# POVRotor.net
KiCad netlist of a schematic drawn in EAGLE
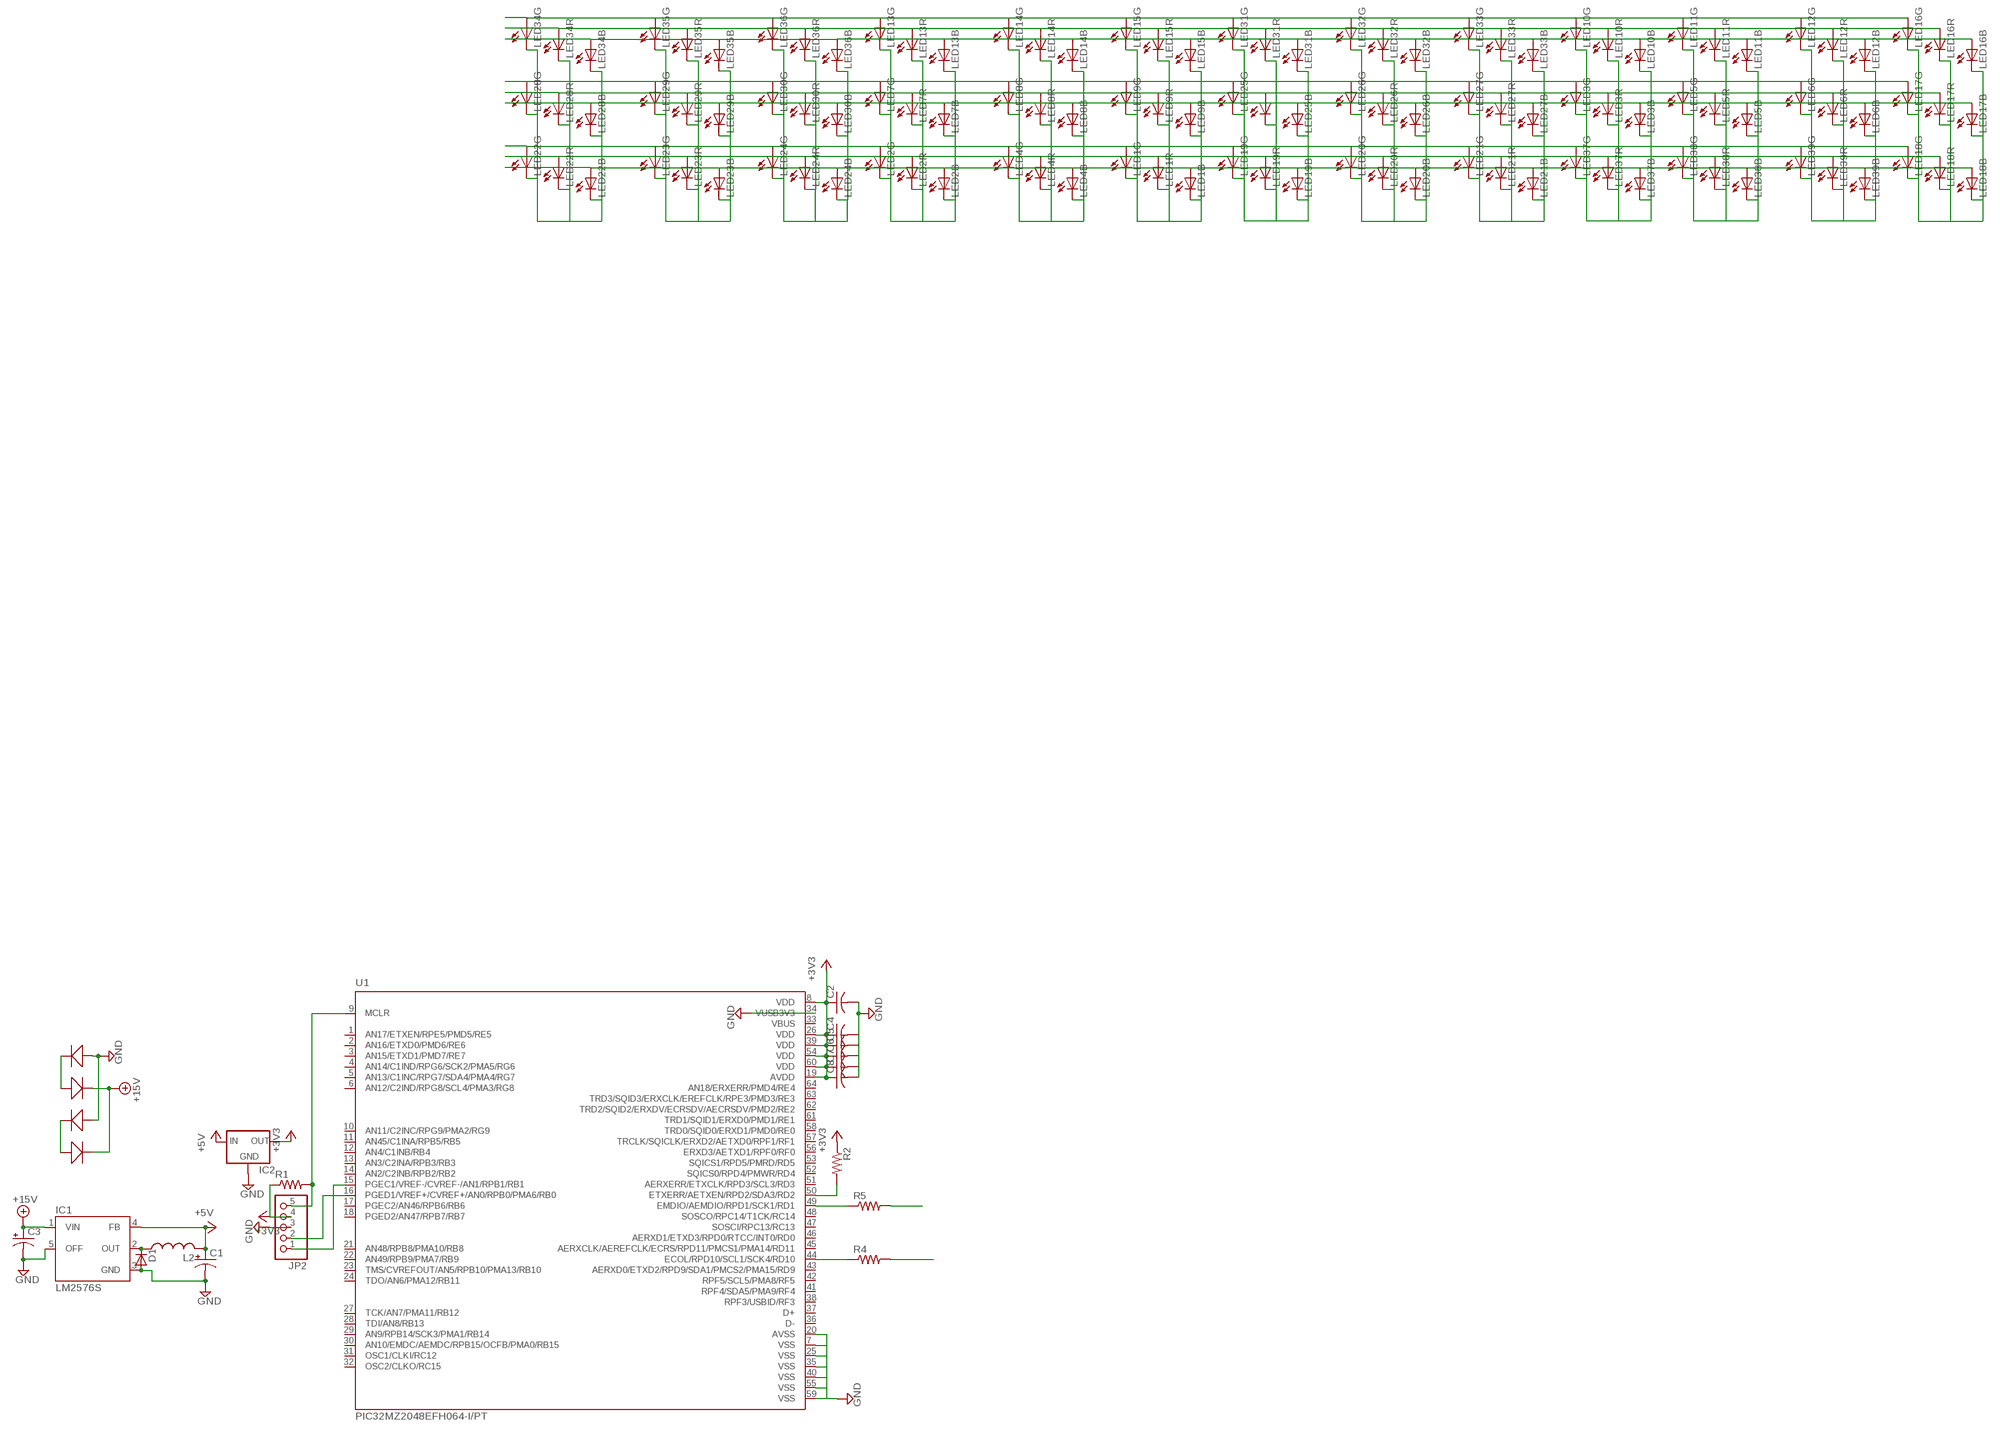
[diagram p0: schematic, sheet 1]

(export (version "E")
  (design (tool "Eeschema 10.0.6"))
  (components
    (comp (ref "C1")
      (value "CPOL-USE2,5-6E")
      (footprint "eagle-import:E2,5-6E")
      (libsource (lib "eagle-import") (part "CPOL-USE2,5-6E"))
    )
    (comp (ref "C2")
      (value "C-USC0805")
      (footprint "eagle-import:C0805")
      (libsource (lib "eagle-import") (part "C-USC0805"))
    )
    (comp (ref "C3")
      (value "CPOL-USE2,5-6E")
      (footprint "eagle-import:E2,5-6E")
      (libsource (lib "eagle-import") (part "CPOL-USE2,5-6E"))
    )
    (comp (ref "C4")
      (value "C-USC0805")
      (footprint "eagle-import:C0805")
      (libsource (lib "eagle-import") (part "C-USC0805"))
    )
    (comp (ref "C5")
      (value "C-USC0805")
      (footprint "eagle-import:C0805")
      (libsource (lib "eagle-import") (part "C-USC0805"))
    )
    (comp (ref "C6")
      (value "C-USC0805")
      (footprint "eagle-import:C0805")
      (libsource (lib "eagle-import") (part "C-USC0805"))
    )
    (comp (ref "C7")
      (value "C-USC0805")
      (footprint "eagle-import:C0805")
      (libsource (lib "eagle-import") (part "C-USC0805"))
    )
    (comp (ref "C8")
      (value "C-USC0805")
      (footprint "eagle-import:C0805")
      (libsource (lib "eagle-import") (part "C-USC0805"))
    )
    (comp (ref "D1")
      (value "BYS10")
      (footprint "eagle-import:SOD106A")
      (fields (field (name "MPN") "BYS10/45"))
      (libsource (lib "eagle-import") (part "BYS10"))
    )
    (comp (ref "D2")
      (value "SMD-DIODE-SCHOTTKY-40V-3A(DO-214AB)")
      (footprint "eagle-import:DO-214AB")
      (fields (field (name "MF") "Vishay") (field (name "MP") "SS34-E3/57T"))
      (libsource (lib "eagle-import") (part "SMD-DIODE-SCHOTTKY-40V-3A(DO-214AB)"))
    )
    (comp (ref "D3")
      (value "SMD-DIODE-SCHOTTKY-40V-3A(DO-214AB)")
      (footprint "eagle-import:DO-214AB")
      (fields (field (name "MF") "Vishay") (field (name "MP") "SS34-E3/57T"))
      (libsource (lib "eagle-import") (part "SMD-DIODE-SCHOTTKY-40V-3A(DO-214AB)"))
    )
    (comp (ref "D4")
      (value "SMD-DIODE-SCHOTTKY-40V-3A(DO-214AB)")
      (footprint "eagle-import:DO-214AB")
      (fields (field (name "MF") "Vishay") (field (name "MP") "SS34-E3/57T"))
      (libsource (lib "eagle-import") (part "SMD-DIODE-SCHOTTKY-40V-3A(DO-214AB)"))
    )
    (comp (ref "D5")
      (value "SMD-DIODE-SCHOTTKY-40V-3A(DO-214AB)")
      (footprint "eagle-import:DO-214AB")
      (fields (field (name "MF") "Vishay") (field (name "MP") "SS34-E3/57T"))
      (libsource (lib "eagle-import") (part "SMD-DIODE-SCHOTTKY-40V-3A(DO-214AB)"))
    )
    (comp (ref "IC1")
      (value "LM2576S")
      (footprint "eagle-import:TO263-5")
      (libsource (lib "eagle-import") (part "LM2576S"))
    )
    (comp (ref "IC2")
      (value "LM1117")
      (footprint "eagle-import:SOT223")
      (libsource (lib "eagle-import") (part "LM1117"))
    )
    (comp (ref "JP2")
      (value "PINHD-1X5")
      (footprint "eagle-import:1X05")
      (libsource (lib "eagle-import") (part "PINHD-1X5"))
    )
    (comp (ref "L2")
      (value "L-USL4532P")
      (footprint "eagle-import:L4532P")
      (libsource (lib "eagle-import") (part "L-USL4532P"))
    )
    (comp (ref "LED1")
      (value "LP2C63-ST-RGB-SR0")
      (footprint "eagle-import:LP2C63-ST-RGB-SR0")
      (libsource (lib "eagle-import") (part "LP2C63-ST-RGB-SR0"))
    )
    (comp (ref "LED2")
      (value "LP2C63-ST-RGB-SR0")
      (footprint "eagle-import:LP2C63-ST-RGB-SR0")
      (libsource (lib "eagle-import") (part "LP2C63-ST-RGB-SR0"))
    )
    (comp (ref "LED3")
      (value "LP2C63-ST-RGB-SR0")
      (footprint "eagle-import:LP2C63-ST-RGB-SR0")
      (libsource (lib "eagle-import") (part "LP2C63-ST-RGB-SR0"))
    )
    (comp (ref "LED4")
      (value "LP2C63-ST-RGB-SR0")
      (footprint "eagle-import:LP2C63-ST-RGB-SR0")
      (libsource (lib "eagle-import") (part "LP2C63-ST-RGB-SR0"))
    )
    (comp (ref "LED5")
      (value "LP2C63-ST-RGB-SR0")
      (footprint "eagle-import:LP2C63-ST-RGB-SR0")
      (libsource (lib "eagle-import") (part "LP2C63-ST-RGB-SR0"))
    )
    (comp (ref "LED6")
      (value "LP2C63-ST-RGB-SR0")
      (footprint "eagle-import:LP2C63-ST-RGB-SR0")
      (libsource (lib "eagle-import") (part "LP2C63-ST-RGB-SR0"))
    )
    (comp (ref "LED7")
      (value "LP2C63-ST-RGB-SR0")
      (footprint "eagle-import:LP2C63-ST-RGB-SR0")
      (libsource (lib "eagle-import") (part "LP2C63-ST-RGB-SR0"))
    )
    (comp (ref "LED8")
      (value "LP2C63-ST-RGB-SR0")
      (footprint "eagle-import:LP2C63-ST-RGB-SR0")
      (libsource (lib "eagle-import") (part "LP2C63-ST-RGB-SR0"))
    )
    (comp (ref "LED9")
      (value "LP2C63-ST-RGB-SR0")
      (footprint "eagle-import:LP2C63-ST-RGB-SR0")
      (libsource (lib "eagle-import") (part "LP2C63-ST-RGB-SR0"))
    )
    (comp (ref "LED10")
      (value "LP2C63-ST-RGB-SR0")
      (footprint "eagle-import:LP2C63-ST-RGB-SR0")
      (libsource (lib "eagle-import") (part "LP2C63-ST-RGB-SR0"))
    )
    (comp (ref "LED11")
      (value "LP2C63-ST-RGB-SR0")
      (footprint "eagle-import:LP2C63-ST-RGB-SR0")
      (libsource (lib "eagle-import") (part "LP2C63-ST-RGB-SR0"))
    )
    (comp (ref "LED12")
      (value "LP2C63-ST-RGB-SR0")
      (footprint "eagle-import:LP2C63-ST-RGB-SR0")
      (libsource (lib "eagle-import") (part "LP2C63-ST-RGB-SR0"))
    )
    (comp (ref "LED13")
      (value "LP2C63-ST-RGB-SR0")
      (footprint "eagle-import:LP2C63-ST-RGB-SR0")
      (libsource (lib "eagle-import") (part "LP2C63-ST-RGB-SR0"))
    )
    (comp (ref "LED14")
      (value "LP2C63-ST-RGB-SR0")
      (footprint "eagle-import:LP2C63-ST-RGB-SR0")
      (libsource (lib "eagle-import") (part "LP2C63-ST-RGB-SR0"))
    )
    (comp (ref "LED15")
      (value "LP2C63-ST-RGB-SR0")
      (footprint "eagle-import:LP2C63-ST-RGB-SR0")
      (libsource (lib "eagle-import") (part "LP2C63-ST-RGB-SR0"))
    )
    (comp (ref "LED16")
      (value "LP2C63-ST-RGB-SR0")
      (footprint "eagle-import:LP2C63-ST-RGB-SR0")
      (libsource (lib "eagle-import") (part "LP2C63-ST-RGB-SR0"))
    )
    (comp (ref "LED17")
      (value "LP2C63-ST-RGB-SR0")
      (footprint "eagle-import:LP2C63-ST-RGB-SR0")
      (libsource (lib "eagle-import") (part "LP2C63-ST-RGB-SR0"))
    )
    (comp (ref "LED18")
      (value "LP2C63-ST-RGB-SR0")
      (footprint "eagle-import:LP2C63-ST-RGB-SR0")
      (libsource (lib "eagle-import") (part "LP2C63-ST-RGB-SR0"))
    )
    (comp (ref "LED19")
      (value "LP2C63-ST-RGB-SR0")
      (footprint "eagle-import:LP2C63-ST-RGB-SR0")
      (libsource (lib "eagle-import") (part "LP2C63-ST-RGB-SR0"))
    )
    (comp (ref "LED20")
      (value "LP2C63-ST-RGB-SR0")
      (footprint "eagle-import:LP2C63-ST-RGB-SR0")
      (libsource (lib "eagle-import") (part "LP2C63-ST-RGB-SR0"))
    )
    (comp (ref "LED21")
      (value "LP2C63-ST-RGB-SR0")
      (footprint "eagle-import:LP2C63-ST-RGB-SR0")
      (libsource (lib "eagle-import") (part "LP2C63-ST-RGB-SR0"))
    )
    (comp (ref "LED22")
      (value "LP2C63-ST-RGB-SR0")
      (footprint "eagle-import:LP2C63-ST-RGB-SR0")
      (libsource (lib "eagle-import") (part "LP2C63-ST-RGB-SR0"))
    )
    (comp (ref "LED23")
      (value "LP2C63-ST-RGB-SR0")
      (footprint "eagle-import:LP2C63-ST-RGB-SR0")
      (libsource (lib "eagle-import") (part "LP2C63-ST-RGB-SR0"))
    )
    (comp (ref "LED24")
      (value "LP2C63-ST-RGB-SR0")
      (footprint "eagle-import:LP2C63-ST-RGB-SR0")
      (libsource (lib "eagle-import") (part "LP2C63-ST-RGB-SR0"))
    )
    (comp (ref "LED25")
      (value "LP2C63-ST-RGB-SR0")
      (footprint "eagle-import:LP2C63-ST-RGB-SR0")
      (libsource (lib "eagle-import") (part "LP2C63-ST-RGB-SR0"))
    )
    (comp (ref "LED26")
      (value "LP2C63-ST-RGB-SR0")
      (footprint "eagle-import:LP2C63-ST-RGB-SR0")
      (libsource (lib "eagle-import") (part "LP2C63-ST-RGB-SR0"))
    )
    (comp (ref "LED27")
      (value "LP2C63-ST-RGB-SR0")
      (footprint "eagle-import:LP2C63-ST-RGB-SR0")
      (libsource (lib "eagle-import") (part "LP2C63-ST-RGB-SR0"))
    )
    (comp (ref "LED28")
      (value "LP2C63-ST-RGB-SR0")
      (footprint "eagle-import:LP2C63-ST-RGB-SR0")
      (libsource (lib "eagle-import") (part "LP2C63-ST-RGB-SR0"))
    )
    (comp (ref "LED29")
      (value "LP2C63-ST-RGB-SR0")
      (footprint "eagle-import:LP2C63-ST-RGB-SR0")
      (libsource (lib "eagle-import") (part "LP2C63-ST-RGB-SR0"))
    )
    (comp (ref "LED30")
      (value "LP2C63-ST-RGB-SR0")
      (footprint "eagle-import:LP2C63-ST-RGB-SR0")
      (libsource (lib "eagle-import") (part "LP2C63-ST-RGB-SR0"))
    )
    (comp (ref "LED31")
      (value "LP2C63-ST-RGB-SR0")
      (footprint "eagle-import:LP2C63-ST-RGB-SR0")
      (libsource (lib "eagle-import") (part "LP2C63-ST-RGB-SR0"))
    )
    (comp (ref "LED32")
      (value "LP2C63-ST-RGB-SR0")
      (footprint "eagle-import:LP2C63-ST-RGB-SR0")
      (libsource (lib "eagle-import") (part "LP2C63-ST-RGB-SR0"))
    )
    (comp (ref "LED33")
      (value "LP2C63-ST-RGB-SR0")
      (footprint "eagle-import:LP2C63-ST-RGB-SR0")
      (libsource (lib "eagle-import") (part "LP2C63-ST-RGB-SR0"))
    )
    (comp (ref "LED34")
      (value "LP2C63-ST-RGB-SR0")
      (footprint "eagle-import:LP2C63-ST-RGB-SR0")
      (libsource (lib "eagle-import") (part "LP2C63-ST-RGB-SR0"))
    )
    (comp (ref "LED35")
      (value "LP2C63-ST-RGB-SR0")
      (footprint "eagle-import:LP2C63-ST-RGB-SR0")
      (libsource (lib "eagle-import") (part "LP2C63-ST-RGB-SR0"))
    )
    (comp (ref "LED36")
      (value "LP2C63-ST-RGB-SR0")
      (footprint "eagle-import:LP2C63-ST-RGB-SR0")
      (libsource (lib "eagle-import") (part "LP2C63-ST-RGB-SR0"))
    )
    (comp (ref "LED37")
      (value "LP2C63-ST-RGB-SR0")
      (footprint "eagle-import:LP2C63-ST-RGB-SR0")
      (libsource (lib "eagle-import") (part "LP2C63-ST-RGB-SR0"))
    )
    (comp (ref "LED38")
      (value "LP2C63-ST-RGB-SR0")
      (footprint "eagle-import:LP2C63-ST-RGB-SR0")
      (libsource (lib "eagle-import") (part "LP2C63-ST-RGB-SR0"))
    )
    (comp (ref "LED39")
      (value "LP2C63-ST-RGB-SR0")
      (footprint "eagle-import:LP2C63-ST-RGB-SR0")
      (libsource (lib "eagle-import") (part "LP2C63-ST-RGB-SR0"))
    )
    (comp (ref "R1")
      (value "R-US_R0805")
      (footprint "eagle-import:R0805")
      (libsource (lib "eagle-import") (part "R-US_R0805"))
    )
    (comp (ref "R2")
      (value "R-US_R0603")
      (footprint "eagle-import:R0603")
      (libsource (lib "eagle-import") (part "R-US_R0603"))
    )
    (comp (ref "R4")
      (value "R-US_R0603")
      (footprint "eagle-import:R0603")
      (libsource (lib "eagle-import") (part "R-US_R0603"))
    )
    (comp (ref "R5")
      (value "R-US_R0603")
      (footprint "eagle-import:R0603")
      (libsource (lib "eagle-import") (part "R-US_R0603"))
    )
    (comp (ref "U1")
      (value "PIC32MZ2048EFH064-I/PT")
      (footprint "eagle-import:QFP50P1200X1200X120-64N")
      (fields (field (name "MF") "Microchip"))
      (libsource (lib "eagle-import") (part "PIC32MZ2048EFH064-I/PT"))
    )
  )
  (nets
    (net (code "1") (name "+3V3") (class "Default")
      (node (ref "C2") (pin "1") (pinfunction "1_1") (pintype "passive"))
      (node (ref "C4") (pin "1") (pinfunction "1_1") (pintype "passive"))
      (node (ref "C5") (pin "1") (pinfunction "1_1") (pintype "passive"))
      (node (ref "C6") (pin "1") (pinfunction "1_1") (pintype "passive"))
      (node (ref "C7") (pin "1") (pinfunction "1_1") (pintype "passive"))
      (node (ref "C8") (pin "1") (pinfunction "1_1") (pintype "passive"))
      (node (ref "IC2") (pin "2") (pinfunction "OUT_2") (pintype "passive"))
      (node (ref "JP2") (pin "4") (pinfunction "4_4") (pintype "passive"))
      (node (ref "R1") (pin "1") (pinfunction "1_1") (pintype "passive"))
      (node (ref "R2") (pin "1") (pinfunction "1_1") (pintype "passive"))
      (node (ref "U1") (pin "19") (pinfunction "AVDD_19") (pintype "power_in"))
      (node (ref "U1") (pin "26") (pinfunction "VDD_26") (pintype "power_in"))
      (node (ref "U1") (pin "39") (pinfunction "VDD_39") (pintype "power_in"))
      (node (ref "U1") (pin "54") (pinfunction "VDD_54") (pintype "power_in"))
      (node (ref "U1") (pin "60") (pinfunction "VDD_60") (pintype "power_in"))
      (node (ref "U1") (pin "8") (pinfunction "VDD_8") (pintype "power_in"))
    )
    (net (code "2") (name "+5V") (class "Default")
      (node (ref "C1") (pin "+") (pinfunction "+_+") (pintype "passive"))
      (node (ref "IC1") (pin "4") (pinfunction "FB_4") (pintype "input"))
      (node (ref "IC2") (pin "3") (pinfunction "IN_3") (pintype "input"))
      (node (ref "L2") (pin "2") (pinfunction "2_2") (pintype "passive"))
    )
    (net (code "3") (name "+15V") (class "Default")
      (node (ref "C3") (pin "+") (pinfunction "+_+") (pintype "passive"))
      (node (ref "D2") (pin "2") (pinfunction "-_2") (pintype "passive"))
      (node (ref "D3") (pin "2") (pinfunction "-_2") (pintype "passive"))
      (node (ref "IC1") (pin "1") (pinfunction "VIN_1") (pintype "power_in"))
    )
    (net (code "4") (name "/VBUS") (class "Default")
      (node (ref "U1") (pin "33") (pinfunction "VBUS_33") (pintype "power_in"))
    )
    (net (code "5") (name "GND") (class "Default")
      (node (ref "C1") (pin "-") (pinfunction "-_-") (pintype "passive"))
      (node (ref "C2") (pin "2") (pinfunction "2_2") (pintype "passive"))
      (node (ref "C3") (pin "-") (pinfunction "-_-") (pintype "passive"))
      (node (ref "C4") (pin "2") (pinfunction "2_2") (pintype "passive"))
      (node (ref "C5") (pin "2") (pinfunction "2_2") (pintype "passive"))
      (node (ref "C6") (pin "2") (pinfunction "2_2") (pintype "passive"))
      (node (ref "C7") (pin "2") (pinfunction "2_2") (pintype "passive"))
      (node (ref "C8") (pin "2") (pinfunction "2_2") (pintype "passive"))
      (node (ref "D1") (pin "A") (pinfunction "A_A") (pintype "passive"))
      (node (ref "D4") (pin "1") (pinfunction "+_1") (pintype "passive"))
      (node (ref "D5") (pin "1") (pinfunction "+_1") (pintype "passive"))
      (node (ref "IC1") (pin "3") (pinfunction "GND_3") (pintype "power_in"))
      (node (ref "IC1") (pin "5") (pinfunction "OFF_5") (pintype "input"))
      (node (ref "IC2") (pin "1") (pinfunction "GND_1") (pintype "input"))
      (node (ref "JP2") (pin "3") (pinfunction "3_3") (pintype "passive"))
      (node (ref "U1") (pin "20") (pinfunction "AVSS_20") (pintype "power_in"))
      (node (ref "U1") (pin "25") (pinfunction "VSS_25") (pintype "power_in"))
      (node (ref "U1") (pin "34") (pinfunction "VUSB3V3_34") (pintype "power_in"))
      (node (ref "U1") (pin "35") (pinfunction "VSS_35") (pintype "power_in"))
      (node (ref "U1") (pin "40") (pinfunction "VSS_40") (pintype "power_in"))
      (node (ref "U1") (pin "55") (pinfunction "VSS_55") (pintype "power_in"))
      (node (ref "U1") (pin "59") (pinfunction "VSS_59") (pintype "power_in"))
      (node (ref "U1") (pin "7") (pinfunction "VSS_7") (pintype "power_in"))
    )
    (net (code "6") (name "Net-(D2-+)") (class "Default")
      (node (ref "D2") (pin "1") (pinfunction "+_1") (pintype "passive"))
      (node (ref "D5") (pin "2") (pinfunction "-_2") (pintype "passive"))
    )
    (net (code "7") (name "Net-(D3-+)") (class "Default")
      (node (ref "D3") (pin "1") (pinfunction "+_1") (pintype "passive"))
      (node (ref "D4") (pin "2") (pinfunction "-_2") (pintype "passive"))
    )
    (net (code "8") (name "Net-(IC1-OUT)") (class "Default")
      (node (ref "D1") (pin "K") (pinfunction "K_K") (pintype "passive"))
      (node (ref "IC1") (pin "2") (pinfunction "OUT_2") (pintype "output"))
      (node (ref "L2") (pin "1") (pinfunction "1_1") (pintype "passive"))
    )
    (net (code "9") (name "Net-(LED10A-A)") (class "Default")
      (node (ref "LED10") (pin "3") (pinfunction "A_3") (pintype "passive"))
      (node (ref "LED11") (pin "3") (pinfunction "A_3") (pintype "passive"))
      (node (ref "LED12") (pin "3") (pinfunction "A_3") (pintype "passive"))
      (node (ref "LED13") (pin "3") (pinfunction "A_3") (pintype "passive"))
      (node (ref "LED14") (pin "3") (pinfunction "A_3") (pintype "passive"))
      (node (ref "LED15") (pin "3") (pinfunction "A_3") (pintype "passive"))
      (node (ref "LED16") (pin "3") (pinfunction "A_3") (pintype "passive"))
      (node (ref "LED31") (pin "3") (pinfunction "A_3") (pintype "passive"))
      (node (ref "LED32") (pin "3") (pinfunction "A_3") (pintype "passive"))
      (node (ref "LED33") (pin "3") (pinfunction "A_3") (pintype "passive"))
      (node (ref "LED34") (pin "3") (pinfunction "A_3") (pintype "passive"))
      (node (ref "LED35") (pin "3") (pinfunction "A_3") (pintype "passive"))
      (node (ref "LED36") (pin "3") (pinfunction "A_3") (pintype "passive"))
    )
    (net (code "10") (name "Net-(LED10A-C)") (class "Default")
      (node (ref "LED10") (pin "4") (pinfunction "C_4") (pintype "passive"))
      (node (ref "LED10") (pin "5") (pinfunction "C_5") (pintype "passive"))
      (node (ref "LED10") (pin "6") (pinfunction "C_6") (pintype "passive"))
      (node (ref "LED3") (pin "4") (pinfunction "C_4") (pintype "passive"))
      (node (ref "LED3") (pin "5") (pinfunction "C_5") (pintype "passive"))
      (node (ref "LED3") (pin "6") (pinfunction "C_6") (pintype "passive"))
      (node (ref "LED37") (pin "4") (pinfunction "C_4") (pintype "passive"))
      (node (ref "LED37") (pin "5") (pinfunction "C_5") (pintype "passive"))
      (node (ref "LED37") (pin "6") (pinfunction "C_6") (pintype "passive"))
    )
    (net (code "11") (name "Net-(LED10B-A)") (class "Default")
      (node (ref "LED10") (pin "1") (pinfunction "A_1") (pintype "passive"))
      (node (ref "LED11") (pin "1") (pinfunction "A_1") (pintype "passive"))
      (node (ref "LED12") (pin "1") (pinfunction "A_1") (pintype "passive"))
      (node (ref "LED13") (pin "1") (pinfunction "A_1") (pintype "passive"))
      (node (ref "LED14") (pin "1") (pinfunction "A_1") (pintype "passive"))
      (node (ref "LED15") (pin "1") (pinfunction "A_1") (pintype "passive"))
      (node (ref "LED16") (pin "1") (pinfunction "A_1") (pintype "passive"))
      (node (ref "LED31") (pin "1") (pinfunction "A_1") (pintype "passive"))
      (node (ref "LED32") (pin "1") (pinfunction "A_1") (pintype "passive"))
      (node (ref "LED33") (pin "1") (pinfunction "A_1") (pintype "passive"))
      (node (ref "LED34") (pin "1") (pinfunction "A_1") (pintype "passive"))
      (node (ref "LED35") (pin "1") (pinfunction "A_1") (pintype "passive"))
      (node (ref "LED36") (pin "1") (pinfunction "A_1") (pintype "passive"))
    )
    (net (code "12") (name "Net-(LED10C-A)") (class "Default")
      (node (ref "LED10") (pin "2") (pinfunction "A_2") (pintype "passive"))
      (node (ref "LED11") (pin "2") (pinfunction "A_2") (pintype "passive"))
      (node (ref "LED12") (pin "2") (pinfunction "A_2") (pintype "passive"))
      (node (ref "LED13") (pin "2") (pinfunction "A_2") (pintype "passive"))
      (node (ref "LED14") (pin "2") (pinfunction "A_2") (pintype "passive"))
      (node (ref "LED15") (pin "2") (pinfunction "A_2") (pintype "passive"))
      (node (ref "LED16") (pin "2") (pinfunction "A_2") (pintype "passive"))
      (node (ref "LED31") (pin "2") (pinfunction "A_2") (pintype "passive"))
      (node (ref "LED32") (pin "2") (pinfunction "A_2") (pintype "passive"))
      (node (ref "LED33") (pin "2") (pinfunction "A_2") (pintype "passive"))
      (node (ref "LED34") (pin "2") (pinfunction "A_2") (pintype "passive"))
      (node (ref "LED35") (pin "2") (pinfunction "A_2") (pintype "passive"))
      (node (ref "LED36") (pin "2") (pinfunction "A_2") (pintype "passive"))
    )
    (net (code "13") (name "Net-(LED11A-C)") (class "Default")
      (node (ref "LED11") (pin "4") (pinfunction "C_4") (pintype "passive"))
      (node (ref "LED11") (pin "5") (pinfunction "C_5") (pintype "passive"))
      (node (ref "LED11") (pin "6") (pinfunction "C_6") (pintype "passive"))
      (node (ref "LED38") (pin "4") (pinfunction "C_4") (pintype "passive"))
      (node (ref "LED38") (pin "5") (pinfunction "C_5") (pintype "passive"))
      (node (ref "LED38") (pin "6") (pinfunction "C_6") (pintype "passive"))
      (node (ref "LED5") (pin "4") (pinfunction "C_4") (pintype "passive"))
      (node (ref "LED5") (pin "5") (pinfunction "C_5") (pintype "passive"))
      (node (ref "LED5") (pin "6") (pinfunction "C_6") (pintype "passive"))
    )
    (net (code "14") (name "Net-(LED12A-C)") (class "Default")
      (node (ref "LED12") (pin "4") (pinfunction "C_4") (pintype "passive"))
      (node (ref "LED12") (pin "5") (pinfunction "C_5") (pintype "passive"))
      (node (ref "LED12") (pin "6") (pinfunction "C_6") (pintype "passive"))
      (node (ref "LED39") (pin "4") (pinfunction "C_4") (pintype "passive"))
      (node (ref "LED39") (pin "5") (pinfunction "C_5") (pintype "passive"))
      (node (ref "LED39") (pin "6") (pinfunction "C_6") (pintype "passive"))
      (node (ref "LED6") (pin "4") (pinfunction "C_4") (pintype "passive"))
      (node (ref "LED6") (pin "5") (pinfunction "C_5") (pintype "passive"))
      (node (ref "LED6") (pin "6") (pinfunction "C_6") (pintype "passive"))
    )
    (net (code "15") (name "Net-(LED13A-C)") (class "Default")
      (node (ref "LED13") (pin "4") (pinfunction "C_4") (pintype "passive"))
      (node (ref "LED13") (pin "5") (pinfunction "C_5") (pintype "passive"))
      (node (ref "LED13") (pin "6") (pinfunction "C_6") (pintype "passive"))
      (node (ref "LED2") (pin "4") (pinfunction "C_4") (pintype "passive"))
      (node (ref "LED2") (pin "5") (pinfunction "C_5") (pintype "passive"))
      (node (ref "LED2") (pin "6") (pinfunction "C_6") (pintype "passive"))
      (node (ref "LED7") (pin "4") (pinfunction "C_4") (pintype "passive"))
      (node (ref "LED7") (pin "5") (pinfunction "C_5") (pintype "passive"))
      (node (ref "LED7") (pin "6") (pinfunction "C_6") (pintype "passive"))
    )
    (net (code "16") (name "Net-(LED14A-C)") (class "Default")
      (node (ref "LED14") (pin "4") (pinfunction "C_4") (pintype "passive"))
      (node (ref "LED14") (pin "5") (pinfunction "C_5") (pintype "passive"))
      (node (ref "LED14") (pin "6") (pinfunction "C_6") (pintype "passive"))
      (node (ref "LED4") (pin "4") (pinfunction "C_4") (pintype "passive"))
      (node (ref "LED4") (pin "5") (pinfunction "C_5") (pintype "passive"))
      (node (ref "LED4") (pin "6") (pinfunction "C_6") (pintype "passive"))
      (node (ref "LED8") (pin "4") (pinfunction "C_4") (pintype "passive"))
      (node (ref "LED8") (pin "5") (pinfunction "C_5") (pintype "passive"))
      (node (ref "LED8") (pin "6") (pinfunction "C_6") (pintype "passive"))
    )
    (net (code "17") (name "Net-(LED15A-C)") (class "Default")
      (node (ref "LED1") (pin "4") (pinfunction "C_4") (pintype "passive"))
      (node (ref "LED1") (pin "5") (pinfunction "C_5") (pintype "passive"))
      (node (ref "LED1") (pin "6") (pinfunction "C_6") (pintype "passive"))
      (node (ref "LED15") (pin "4") (pinfunction "C_4") (pintype "passive"))
      (node (ref "LED15") (pin "5") (pinfunction "C_5") (pintype "passive"))
      (node (ref "LED15") (pin "6") (pinfunction "C_6") (pintype "passive"))
      (node (ref "LED9") (pin "4") (pinfunction "C_4") (pintype "passive"))
      (node (ref "LED9") (pin "5") (pinfunction "C_5") (pintype "passive"))
      (node (ref "LED9") (pin "6") (pinfunction "C_6") (pintype "passive"))
    )
    (net (code "18") (name "Net-(LED16A-C)") (class "Default")
      (node (ref "LED16") (pin "4") (pinfunction "C_4") (pintype "passive"))
      (node (ref "LED16") (pin "5") (pinfunction "C_5") (pintype "passive"))
      (node (ref "LED16") (pin "6") (pinfunction "C_6") (pintype "passive"))
      (node (ref "LED17") (pin "4") (pinfunction "C_4") (pintype "passive"))
      (node (ref "LED17") (pin "5") (pinfunction "C_5") (pintype "passive"))
      (node (ref "LED17") (pin "6") (pinfunction "C_6") (pintype "passive"))
      (node (ref "LED18") (pin "4") (pinfunction "C_4") (pintype "passive"))
      (node (ref "LED18") (pin "5") (pinfunction "C_5") (pintype "passive"))
      (node (ref "LED18") (pin "6") (pinfunction "C_6") (pintype "passive"))
    )
    (net (code "19") (name "Net-(LED17A-A)") (class "Default")
      (node (ref "LED17") (pin "3") (pinfunction "A_3") (pintype "passive"))
      (node (ref "LED26") (pin "3") (pinfunction "A_3") (pintype "passive"))
      (node (ref "LED27") (pin "3") (pinfunction "A_3") (pintype "passive"))
      (node (ref "LED28") (pin "3") (pinfunction "A_3") (pintype "passive"))
      (node (ref "LED29") (pin "3") (pinfunction "A_3") (pintype "passive"))
      (node (ref "LED3") (pin "3") (pinfunction "A_3") (pintype "passive"))
      (node (ref "LED30") (pin "3") (pinfunction "A_3") (pintype "passive"))
      (node (ref "LED5") (pin "3") (pinfunction "A_3") (pintype "passive"))
      (node (ref "LED6") (pin "3") (pinfunction "A_3") (pintype "passive"))
      (node (ref "LED8") (pin "3") (pinfunction "A_3") (pintype "passive"))
      (node (ref "LED9") (pin "3") (pinfunction "A_3") (pintype "passive"))
    )
    (net (code "20") (name "Net-(LED17B-A)") (class "Default")
      (node (ref "LED17") (pin "1") (pinfunction "A_1") (pintype "passive"))
      (node (ref "LED25") (pin "1") (pinfunction "A_1") (pintype "passive"))
      (node (ref "LED26") (pin "1") (pinfunction "A_1") (pintype "passive"))
      (node (ref "LED27") (pin "1") (pinfunction "A_1") (pintype "passive"))
      (node (ref "LED28") (pin "1") (pinfunction "A_1") (pintype "passive"))
      (node (ref "LED29") (pin "1") (pinfunction "A_1") (pintype "passive"))
      (node (ref "LED3") (pin "1") (pinfunction "A_1") (pintype "passive"))
      (node (ref "LED30") (pin "1") (pinfunction "A_1") (pintype "passive"))
      (node (ref "LED5") (pin "1") (pinfunction "A_1") (pintype "passive"))
      (node (ref "LED6") (pin "1") (pinfunction "A_1") (pintype "passive"))
      (node (ref "LED7") (pin "1") (pinfunction "A_1") (pintype "passive"))
      (node (ref "LED8") (pin "1") (pinfunction "A_1") (pintype "passive"))
      (node (ref "LED9") (pin "1") (pinfunction "A_1") (pintype "passive"))
    )
    (net (code "21") (name "Net-(LED17C-A)") (class "Default")
      (node (ref "LED17") (pin "2") (pinfunction "A_2") (pintype "passive"))
      (node (ref "LED25") (pin "2") (pinfunction "A_2") (pintype "passive"))
      (node (ref "LED26") (pin "2") (pinfunction "A_2") (pintype "passive"))
      (node (ref "LED27") (pin "2") (pinfunction "A_2") (pintype "passive"))
      (node (ref "LED28") (pin "2") (pinfunction "A_2") (pintype "passive"))
      (node (ref "LED29") (pin "2") (pinfunction "A_2") (pintype "passive"))
      (node (ref "LED3") (pin "2") (pinfunction "A_2") (pintype "passive"))
      (node (ref "LED30") (pin "2") (pinfunction "A_2") (pintype "passive"))
      (node (ref "LED5") (pin "2") (pinfunction "A_2") (pintype "passive"))
      (node (ref "LED6") (pin "2") (pinfunction "A_2") (pintype "passive"))
      (node (ref "LED7") (pin "2") (pinfunction "A_2") (pintype "passive"))
      (node (ref "LED8") (pin "2") (pinfunction "A_2") (pintype "passive"))
      (node (ref "LED9") (pin "2") (pinfunction "A_2") (pintype "passive"))
    )
    (net (code "22") (name "Net-(LED18A-A)") (class "Default")
      (node (ref "LED1") (pin "3") (pinfunction "A_3") (pintype "passive"))
      (node (ref "LED18") (pin "3") (pinfunction "A_3") (pintype "passive"))
      (node (ref "LED19") (pin "3") (pinfunction "A_3") (pintype "passive"))
      (node (ref "LED2") (pin "3") (pinfunction "A_3") (pintype "passive"))
      (node (ref "LED20") (pin "3") (pinfunction "A_3") (pintype "passive"))
      (node (ref "LED21") (pin "3") (pinfunction "A_3") (pintype "passive"))
      (node (ref "LED22") (pin "3") (pinfunction "A_3") (pintype "passive"))
      (node (ref "LED23") (pin "3") (pinfunction "A_3") (pintype "passive"))
      (node (ref "LED24") (pin "3") (pinfunction "A_3") (pintype "passive"))
      (node (ref "LED37") (pin "3") (pinfunction "A_3") (pintype "passive"))
      (node (ref "LED38") (pin "3") (pinfunction "A_3") (pintype "passive"))
      (node (ref "LED39") (pin "3") (pinfunction "A_3") (pintype "passive"))
      (node (ref "LED4") (pin "3") (pinfunction "A_3") (pintype "passive"))
    )
    (net (code "23") (name "Net-(LED18B-A)") (class "Default")
      (node (ref "LED1") (pin "1") (pinfunction "A_1") (pintype "passive"))
      (node (ref "LED18") (pin "1") (pinfunction "A_1") (pintype "passive"))
      (node (ref "LED19") (pin "1") (pinfunction "A_1") (pintype "passive"))
      (node (ref "LED2") (pin "1") (pinfunction "A_1") (pintype "passive"))
      (node (ref "LED20") (pin "1") (pinfunction "A_1") (pintype "passive"))
      (node (ref "LED21") (pin "1") (pinfunction "A_1") (pintype "passive"))
      (node (ref "LED22") (pin "1") (pinfunction "A_1") (pintype "passive"))
      (node (ref "LED23") (pin "1") (pinfunction "A_1") (pintype "passive"))
      (node (ref "LED24") (pin "1") (pinfunction "A_1") (pintype "passive"))
      (node (ref "LED37") (pin "1") (pinfunction "A_1") (pintype "passive"))
      (node (ref "LED38") (pin "1") (pinfunction "A_1") (pintype "passive"))
      (node (ref "LED39") (pin "1") (pinfunction "A_1") (pintype "passive"))
      (node (ref "LED4") (pin "1") (pinfunction "A_1") (pintype "passive"))
    )
    (net (code "24") (name "Net-(LED18C-A)") (class "Default")
      (node (ref "LED1") (pin "2") (pinfunction "A_2") (pintype "passive"))
      (node (ref "LED18") (pin "2") (pinfunction "A_2") (pintype "passive"))
      (node (ref "LED19") (pin "2") (pinfunction "A_2") (pintype "passive"))
      (node (ref "LED2") (pin "2") (pinfunction "A_2") (pintype "passive"))
      (node (ref "LED20") (pin "2") (pinfunction "A_2") (pintype "passive"))
      (node (ref "LED21") (pin "2") (pinfunction "A_2") (pintype "passive"))
      (node (ref "LED22") (pin "2") (pinfunction "A_2") (pintype "passive"))
      (node (ref "LED23") (pin "2") (pinfunction "A_2") (pintype "passive"))
      (node (ref "LED24") (pin "2") (pinfunction "A_2") (pintype "passive"))
      (node (ref "LED37") (pin "2") (pinfunction "A_2") (pintype "passive"))
      (node (ref "LED38") (pin "2") (pinfunction "A_2") (pintype "passive"))
      (node (ref "LED39") (pin "2") (pinfunction "A_2") (pintype "passive"))
      (node (ref "LED4") (pin "2") (pinfunction "A_2") (pintype "passive"))
    )
    (net (code "25") (name "Net-(LED19A-C)") (class "Default")
      (node (ref "LED19") (pin "4") (pinfunction "C_4") (pintype "passive"))
      (node (ref "LED19") (pin "5") (pinfunction "C_5") (pintype "passive"))
      (node (ref "LED19") (pin "6") (pinfunction "C_6") (pintype "passive"))
      (node (ref "LED25") (pin "4") (pinfunction "C_4") (pintype "passive"))
      (node (ref "LED25") (pin "5") (pinfunction "C_5") (pintype "passive"))
      (node (ref "LED25") (pin "6") (pinfunction "C_6") (pintype "passive"))
      (node (ref "LED31") (pin "4") (pinfunction "C_4") (pintype "passive"))
      (node (ref "LED31") (pin "5") (pinfunction "C_5") (pintype "passive"))
      (node (ref "LED31") (pin "6") (pinfunction "C_6") (pintype "passive"))
    )
    (net (code "26") (name "Net-(LED20A-C)") (class "Default")
      (node (ref "LED20") (pin "4") (pinfunction "C_4") (pintype "passive"))
      (node (ref "LED20") (pin "5") (pinfunction "C_5") (pintype "passive"))
      (node (ref "LED20") (pin "6") (pinfunction "C_6") (pintype "passive"))
      (node (ref "LED26") (pin "4") (pinfunction "C_4") (pintype "passive"))
      (node (ref "LED26") (pin "5") (pinfunction "C_5") (pintype "passive"))
      (node (ref "LED32") (pin "4") (pinfunction "C_4") (pintype "passive"))
      (node (ref "LED32") (pin "5") (pinfunction "C_5") (pintype "passive"))
      (node (ref "LED32") (pin "6") (pinfunction "C_6") (pintype "passive"))
    )
    (net (code "27") (name "Net-(LED21A-C)") (class "Default")
      (node (ref "LED21") (pin "4") (pinfunction "C_4") (pintype "passive"))
      (node (ref "LED21") (pin "5") (pinfunction "C_5") (pintype "passive"))
      (node (ref "LED21") (pin "6") (pinfunction "C_6") (pintype "passive"))
      (node (ref "LED27") (pin "4") (pinfunction "C_4") (pintype "passive"))
      (node (ref "LED27") (pin "5") (pinfunction "C_5") (pintype "passive"))
      (node (ref "LED27") (pin "6") (pinfunction "C_6") (pintype "passive"))
      (node (ref "LED33") (pin "4") (pinfunction "C_4") (pintype "passive"))
      (node (ref "LED33") (pin "5") (pinfunction "C_5") (pintype "passive"))
      (node (ref "LED33") (pin "6") (pinfunction "C_6") (pintype "passive"))
    )
    (net (code "28") (name "Net-(LED22A-C)") (class "Default")
      (node (ref "LED22") (pin "4") (pinfunction "C_4") (pintype "passive"))
      (node (ref "LED22") (pin "5") (pinfunction "C_5") (pintype "passive"))
      (node (ref "LED22") (pin "6") (pinfunction "C_6") (pintype "passive"))
      (node (ref "LED28") (pin "4") (pinfunction "C_4") (pintype "passive"))
      (node (ref "LED28") (pin "5") (pinfunction "C_5") (pintype "passive"))
      (node (ref "LED28") (pin "6") (pinfunction "C_6") (pintype "passive"))
      (node (ref "LED34") (pin "4") (pinfunction "C_4") (pintype "passive"))
      (node (ref "LED34") (pin "5") (pinfunction "C_5") (pintype "passive"))
      (node (ref "LED34") (pin "6") (pinfunction "C_6") (pintype "passive"))
    )
    (net (code "29") (name "Net-(LED23A-C)") (class "Default")
      (node (ref "LED23") (pin "4") (pinfunction "C_4") (pintype "passive"))
      (node (ref "LED23") (pin "5") (pinfunction "C_5") (pintype "passive"))
      (node (ref "LED23") (pin "6") (pinfunction "C_6") (pintype "passive"))
      (node (ref "LED29") (pin "4") (pinfunction "C_4") (pintype "passive"))
      (node (ref "LED29") (pin "5") (pinfunction "C_5") (pintype "passive"))
      (node (ref "LED29") (pin "6") (pinfunction "C_6") (pintype "passive"))
      (node (ref "LED35") (pin "4") (pinfunction "C_4") (pintype "passive"))
      (node (ref "LED35") (pin "5") (pinfunction "C_5") (pintype "passive"))
      (node (ref "LED35") (pin "6") (pinfunction "C_6") (pintype "passive"))
    )
    (net (code "30") (name "Net-(LED24A-C)") (class "Default")
      (node (ref "LED24") (pin "4") (pinfunction "C_4") (pintype "passive"))
      (node (ref "LED24") (pin "5") (pinfunction "C_5") (pintype "passive"))
      (node (ref "LED24") (pin "6") (pinfunction "C_6") (pintype "passive"))
      (node (ref "LED30") (pin "4") (pinfunction "C_4") (pintype "passive"))
      (node (ref "LED30") (pin "5") (pinfunction "C_5") (pintype "passive"))
      (node (ref "LED30") (pin "6") (pinfunction "C_6") (pintype "passive"))
      (node (ref "LED36") (pin "4") (pinfunction "C_4") (pintype "passive"))
      (node (ref "LED36") (pin "5") (pinfunction "C_5") (pintype "passive"))
      (node (ref "LED36") (pin "6") (pinfunction "C_6") (pintype "passive"))
    )
    (net (code "31") (name "Net-(U1-ECOL{slash}RPD10{slash}SCL1{slash}SCK4{slash}RD10)") (class "Default")
      (node (ref "R4") (pin "1") (pinfunction "1_1") (pintype "passive"))
      (node (ref "U1") (pin "44") (pinfunction "ECOL/RPD10/SCL1/SCK4/RD10_44") (pintype "bidirectional"))
    )
    (net (code "32") (name "Net-(U1-EMDIO{slash}AEMDIO{slash}RPD1{slash}SCK1{slash}RD1)") (class "Default")
      (node (ref "R5") (pin "1") (pinfunction "1_1") (pintype "passive"))
      (node (ref "U1") (pin "49") (pinfunction "EMDIO/AEMDIO/RPD1/SCK1/RD1_49") (pintype "bidirectional"))
    )
    (net (code "33") (name "Net-(U1-ETXERR{slash}AETXEN{slash}RPD2{slash}SDA3{slash}RD2)") (class "Default")
      (node (ref "R2") (pin "2") (pinfunction "2_2") (pintype "passive"))
      (node (ref "U1") (pin "50") (pinfunction "ETXERR/AETXEN/RPD2/SDA3/RD2_50") (pintype "bidirectional"))
    )
    (net (code "34") (name "Net-(U1-MCLR)") (class "Default")
      (node (ref "JP2") (pin "5") (pinfunction "5_5") (pintype "passive"))
      (node (ref "R1") (pin "2") (pinfunction "2_2") (pintype "passive"))
      (node (ref "U1") (pin "9") (pinfunction "MCLR_9") (pintype "input"))
    )
    (net (code "35") (name "Net-(U1-PGEC1{slash}VREF-{slash}CVREF-{slash}AN1{slash}RPB1{slash}RB1)") (class "Default")
      (node (ref "JP2") (pin "1") (pinfunction "1_1") (pintype "passive"))
      (node (ref "U1") (pin "15") (pinfunction "PGEC1/VREF-/CVREF-/AN1/RPB1/RB1_15") (pintype "bidirectional"))
    )
    (net (code "36") (name "Net-(U1-PGED1{slash}VREF+{slash}CVREF+{slash}AN0{slash}RPB0{slash}PMA6{slash}RB0)") (class "Default")
      (node (ref "JP2") (pin "2") (pinfunction "2_2") (pintype "passive"))
      (node (ref "U1") (pin "16") (pinfunction "PGED1/VREF+/CVREF+/AN0/RPB0/PMA6/RB0_16") (pintype "bidirectional"))
    )
    (net (code "37") (name "unconnected-(LED7A-A-Pad3)") (class "Default")
      (node (ref "LED7") (pin "3") (pinfunction "A_3") (pintype "passive"))
    )
    (net (code "38") (name "unconnected-(LED25A-A-Pad3)") (class "Default")
      (node (ref "LED25") (pin "3") (pinfunction "A_3") (pintype "passive"))
    )
    (net (code "39") (name "unconnected-(LED26B-C-Pad6)") (class "Default")
      (node (ref "LED26") (pin "6") (pinfunction "C_6") (pintype "passive"))
    )
    (net (code "40") (name "unconnected-(R4-Pad2)") (class "Default")
      (node (ref "R4") (pin "2") (pinfunction "2_2") (pintype "passive"))
    )
    (net (code "41") (name "unconnected-(R5-Pad2)") (class "Default")
      (node (ref "R5") (pin "2") (pinfunction "2_2") (pintype "passive"))
    )
    (net (code "42") (name "unconnected-(U1-AERXCLK{slash}AEREFCLK{slash}ECRS{slash}RPD11{slash}PMCS1{slash}PMA14{slash}RD11-Pad45)") (class "Default")
      (node (ref "U1") (pin "45") (pinfunction "AERXCLK/AEREFCLK/ECRS/RPD11/PMCS1/PMA14/RD11_45") (pintype "bidirectional"))
    )
    (net (code "43") (name "unconnected-(U1-AERXD0{slash}ETXD2{slash}RPD9{slash}SDA1{slash}PMCS2{slash}PMA15{slash}RD9-Pad43)") (class "Default")
      (node (ref "U1") (pin "43") (pinfunction "AERXD0/ETXD2/RPD9/SDA1/PMCS2/PMA15/RD9_43") (pintype "bidirectional"))
    )
    (net (code "44") (name "unconnected-(U1-AERXD1{slash}ETXD3{slash}RPD0{slash}RTCC{slash}INT0{slash}RD0-Pad46)") (class "Default")
      (node (ref "U1") (pin "46") (pinfunction "AERXD1/ETXD3/RPD0/RTCC/INT0/RD0_46") (pintype "bidirectional"))
    )
    (net (code "45") (name "unconnected-(U1-AERXERR{slash}ETXCLK{slash}RPD3{slash}SCL3{slash}RD3-Pad51)") (class "Default")
      (node (ref "U1") (pin "51") (pinfunction "AERXERR/ETXCLK/RPD3/SCL3/RD3_51") (pintype "bidirectional"))
    )
    (net (code "46") (name "unconnected-(U1-AN2{slash}C2INB{slash}RPB2{slash}RB2-Pad14)") (class "Default")
      (node (ref "U1") (pin "14") (pinfunction "AN2/C2INB/RPB2/RB2_14") (pintype "bidirectional"))
    )
    (net (code "47") (name "unconnected-(U1-AN3{slash}C2INA{slash}RPB3{slash}RB3-Pad13)") (class "Default")
      (node (ref "U1") (pin "13") (pinfunction "AN3/C2INA/RPB3/RB3_13") (pintype "bidirectional"))
    )
    (net (code "48") (name "unconnected-(U1-AN4{slash}C1INB{slash}RB4-Pad12)") (class "Default")
      (node (ref "U1") (pin "12") (pinfunction "AN4/C1INB/RB4_12") (pintype "bidirectional"))
    )
    (net (code "49") (name "unconnected-(U1-AN9{slash}RPB14{slash}SCK3{slash}PMA1{slash}RB14-Pad29)") (class "Default")
      (node (ref "U1") (pin "29") (pinfunction "AN9/RPB14/SCK3/PMA1/RB14_29") (pintype "bidirectional"))
    )
    (net (code "50") (name "unconnected-(U1-AN10{slash}EMDC{slash}AEMDC{slash}RPB15{slash}OCFB{slash}PMA0{slash}RB15-Pad30)") (class "Default")
      (node (ref "U1") (pin "30") (pinfunction "AN10/EMDC/AEMDC/RPB15/OCFB/PMA0/RB15_30") (pintype "bidirectional"))
    )
    (net (code "51") (name "unconnected-(U1-AN11{slash}C2INC{slash}RPG9{slash}PMA2{slash}RG9-Pad10)") (class "Default")
      (node (ref "U1") (pin "10") (pinfunction "AN11/C2INC/RPG9/PMA2/RG9_10") (pintype "bidirectional"))
    )
    (net (code "52") (name "unconnected-(U1-AN12{slash}C2IND{slash}RPG8{slash}SCL4{slash}PMA3{slash}RG8-Pad6)") (class "Default")
      (node (ref "U1") (pin "6") (pinfunction "AN12/C2IND/RPG8/SCL4/PMA3/RG8_6") (pintype "bidirectional"))
    )
    (net (code "53") (name "unconnected-(U1-AN13{slash}C1INC{slash}RPG7{slash}SDA4{slash}PMA4{slash}RG7-Pad5)") (class "Default")
      (node (ref "U1") (pin "5") (pinfunction "AN13/C1INC/RPG7/SDA4/PMA4/RG7_5") (pintype "bidirectional"))
    )
    (net (code "54") (name "unconnected-(U1-AN14{slash}C1IND{slash}RPG6{slash}SCK2{slash}PMA5{slash}RG6-Pad4)") (class "Default")
      (node (ref "U1") (pin "4") (pinfunction "AN14/C1IND/RPG6/SCK2/PMA5/RG6_4") (pintype "bidirectional"))
    )
    (net (code "55") (name "unconnected-(U1-AN15{slash}ETXD1{slash}PMD7{slash}RE7-Pad3)") (class "Default")
      (node (ref "U1") (pin "3") (pinfunction "AN15/ETXD1/PMD7/RE7_3") (pintype "bidirectional"))
    )
    (net (code "56") (name "unconnected-(U1-AN16{slash}ETXD0{slash}PMD6{slash}RE6-Pad2)") (class "Default")
      (node (ref "U1") (pin "2") (pinfunction "AN16/ETXD0/PMD6/RE6_2") (pintype "bidirectional"))
    )
    (net (code "57") (name "unconnected-(U1-AN17{slash}ETXEN{slash}RPE5{slash}PMD5{slash}RE5-Pad1)") (class "Default")
      (node (ref "U1") (pin "1") (pinfunction "AN17/ETXEN/RPE5/PMD5/RE5_1") (pintype "bidirectional"))
    )
    (net (code "58") (name "unconnected-(U1-AN18{slash}ERXERR{slash}PMD4{slash}RE4-Pad64)") (class "Default")
      (node (ref "U1") (pin "64") (pinfunction "AN18/ERXERR/PMD4/RE4_64") (pintype "bidirectional"))
    )
    (net (code "59") (name "unconnected-(U1-AN45{slash}C1INA{slash}RPB5{slash}RB5-Pad11)") (class "Default")
      (node (ref "U1") (pin "11") (pinfunction "AN45/C1INA/RPB5/RB5_11") (pintype "bidirectional"))
    )
    (net (code "60") (name "unconnected-(U1-AN48{slash}RPB8{slash}PMA10{slash}RB8-Pad21)") (class "Default")
      (node (ref "U1") (pin "21") (pinfunction "AN48/RPB8/PMA10/RB8_21") (pintype "bidirectional"))
    )
    (net (code "61") (name "unconnected-(U1-AN49{slash}RPB9{slash}PMA7{slash}RB9-Pad22)") (class "Default")
      (node (ref "U1") (pin "22") (pinfunction "AN49/RPB9/PMA7/RB9_22") (pintype "bidirectional"))
    )
    (net (code "62") (name "unconnected-(U1-D+-Pad37)") (class "Default")
      (node (ref "U1") (pin "37") (pinfunction "D+_37") (pintype "bidirectional"))
    )
    (net (code "63") (name "unconnected-(U1-D--Pad36)") (class "Default")
      (node (ref "U1") (pin "36") (pinfunction "D-_36") (pintype "bidirectional"))
    )
    (net (code "64") (name "unconnected-(U1-ERXD3{slash}AETXD1{slash}RPF0{slash}RF0-Pad56)") (class "Default")
      (node (ref "U1") (pin "56") (pinfunction "ERXD3/AETXD1/RPF0/RF0_56") (pintype "bidirectional"))
    )
    (net (code "65") (name "unconnected-(U1-OSC1{slash}CLKI{slash}RC12-Pad31)") (class "Default")
      (node (ref "U1") (pin "31") (pinfunction "OSC1/CLKI/RC12_31") (pintype "bidirectional"))
    )
    (net (code "66") (name "unconnected-(U1-OSC2{slash}CLKO{slash}RC15-Pad32)") (class "Default")
      (node (ref "U1") (pin "32") (pinfunction "OSC2/CLKO/RC15_32") (pintype "bidirectional"))
    )
    (net (code "67") (name "unconnected-(U1-PGEC2{slash}AN46{slash}RPB6{slash}RB6-Pad17)") (class "Default")
      (node (ref "U1") (pin "17") (pinfunction "PGEC2/AN46/RPB6/RB6_17") (pintype "bidirectional"))
    )
    (net (code "68") (name "unconnected-(U1-PGED2{slash}AN47{slash}RPB7{slash}RB7-Pad18)") (class "Default")
      (node (ref "U1") (pin "18") (pinfunction "PGED2/AN47/RPB7/RB7_18") (pintype "bidirectional"))
    )
    (net (code "69") (name "unconnected-(U1-RPF3{slash}USBID{slash}RF3-Pad38)") (class "Default")
      (node (ref "U1") (pin "38") (pinfunction "RPF3/USBID/RF3_38") (pintype "bidirectional"))
    )
    (net (code "70") (name "unconnected-(U1-RPF4{slash}SDA5{slash}PMA9{slash}RF4-Pad41)") (class "Default")
      (node (ref "U1") (pin "41") (pinfunction "RPF4/SDA5/PMA9/RF4_41") (pintype "bidirectional"))
    )
    (net (code "71") (name "unconnected-(U1-RPF5{slash}SCL5{slash}PMA8{slash}RF5-Pad42)") (class "Default")
      (node (ref "U1") (pin "42") (pinfunction "RPF5/SCL5/PMA8/RF5_42") (pintype "bidirectional"))
    )
    (net (code "72") (name "unconnected-(U1-SOSCI{slash}RPC13{slash}RC13-Pad47)") (class "Default")
      (node (ref "U1") (pin "47") (pinfunction "SOSCI/RPC13/RC13_47") (pintype "bidirectional"))
    )
    (net (code "73") (name "unconnected-(U1-SOSCO{slash}RPC14{slash}T1CK{slash}RC14-Pad48)") (class "Default")
      (node (ref "U1") (pin "48") (pinfunction "SOSCO/RPC14/T1CK/RC14_48") (pintype "bidirectional"))
    )
    (net (code "74") (name "unconnected-(U1-SQICS0{slash}RPD4{slash}PMWR{slash}RD4-Pad52)") (class "Default")
      (node (ref "U1") (pin "52") (pinfunction "SQICS0/RPD4/PMWR/RD4_52") (pintype "bidirectional"))
    )
    (net (code "75") (name "unconnected-(U1-SQICS1{slash}RPD5{slash}PMRD{slash}RD5-Pad53)") (class "Default")
      (node (ref "U1") (pin "53") (pinfunction "SQICS1/RPD5/PMRD/RD5_53") (pintype "bidirectional"))
    )
    (net (code "76") (name "unconnected-(U1-TCK{slash}AN7{slash}PMA11{slash}RB12-Pad27)") (class "Default")
      (node (ref "U1") (pin "27") (pinfunction "TCK/AN7/PMA11/RB12_27") (pintype "bidirectional"))
    )
    (net (code "77") (name "unconnected-(U1-TDI{slash}AN8{slash}RB13-Pad28)") (class "Default")
      (node (ref "U1") (pin "28") (pinfunction "TDI/AN8/RB13_28") (pintype "bidirectional"))
    )
    (net (code "78") (name "unconnected-(U1-TDO{slash}AN6{slash}PMA12{slash}RB11-Pad24)") (class "Default")
      (node (ref "U1") (pin "24") (pinfunction "TDO/AN6/PMA12/RB11_24") (pintype "bidirectional"))
    )
    (net (code "79") (name "unconnected-(U1-TMS{slash}CVREFOUT{slash}AN5{slash}RPB10{slash}PMA13{slash}RB10-Pad23)") (class "Default")
      (node (ref "U1") (pin "23") (pinfunction "TMS/CVREFOUT/AN5/RPB10/PMA13/RB10_23") (pintype "bidirectional"))
    )
    (net (code "80") (name "unconnected-(U1-TRCLK{slash}SQICLK{slash}ERXD2{slash}AETXD0{slash}RPF1{slash}RF1-Pad57)") (class "Default")
      (node (ref "U1") (pin "57") (pinfunction "TRCLK/SQICLK/ERXD2/AETXD0/RPF1/RF1_57") (pintype "bidirectional"))
    )
    (net (code "81") (name "unconnected-(U1-TRD0{slash}SQID0{slash}ERXD1{slash}PMD0{slash}RE0-Pad58)") (class "Default")
      (node (ref "U1") (pin "58") (pinfunction "TRD0/SQID0/ERXD1/PMD0/RE0_58") (pintype "bidirectional"))
    )
    (net (code "82") (name "unconnected-(U1-TRD1{slash}SQID1{slash}ERXD0{slash}PMD1{slash}RE1-Pad61)") (class "Default")
      (node (ref "U1") (pin "61") (pinfunction "TRD1/SQID1/ERXD0/PMD1/RE1_61") (pintype "bidirectional"))
    )
    (net (code "83") (name "unconnected-(U1-TRD2{slash}SQID2{slash}ERXDV{slash}ECRSDV{slash}AECRSDV{slash}PMD2{slash}RE2-Pad62)") (class "Default")
      (node (ref "U1") (pin "62") (pinfunction "TRD2/SQID2/ERXDV/ECRSDV/AECRSDV/PMD2/RE2_62") (pintype "bidirectional"))
    )
    (net (code "84") (name "unconnected-(U1-TRD3{slash}SQID3{slash}ERXCLK{slash}EREFCLK{slash}RPE3{slash}PMD3{slash}RE3-Pad63)") (class "Default")
      (node (ref "U1") (pin "63") (pinfunction "TRD3/SQID3/ERXCLK/EREFCLK/RPE3/PMD3/RE3_63") (pintype "bidirectional"))
    )
  )
)
